# board_ders.net
KiCad netlist of a schematic drawn in EAGLE
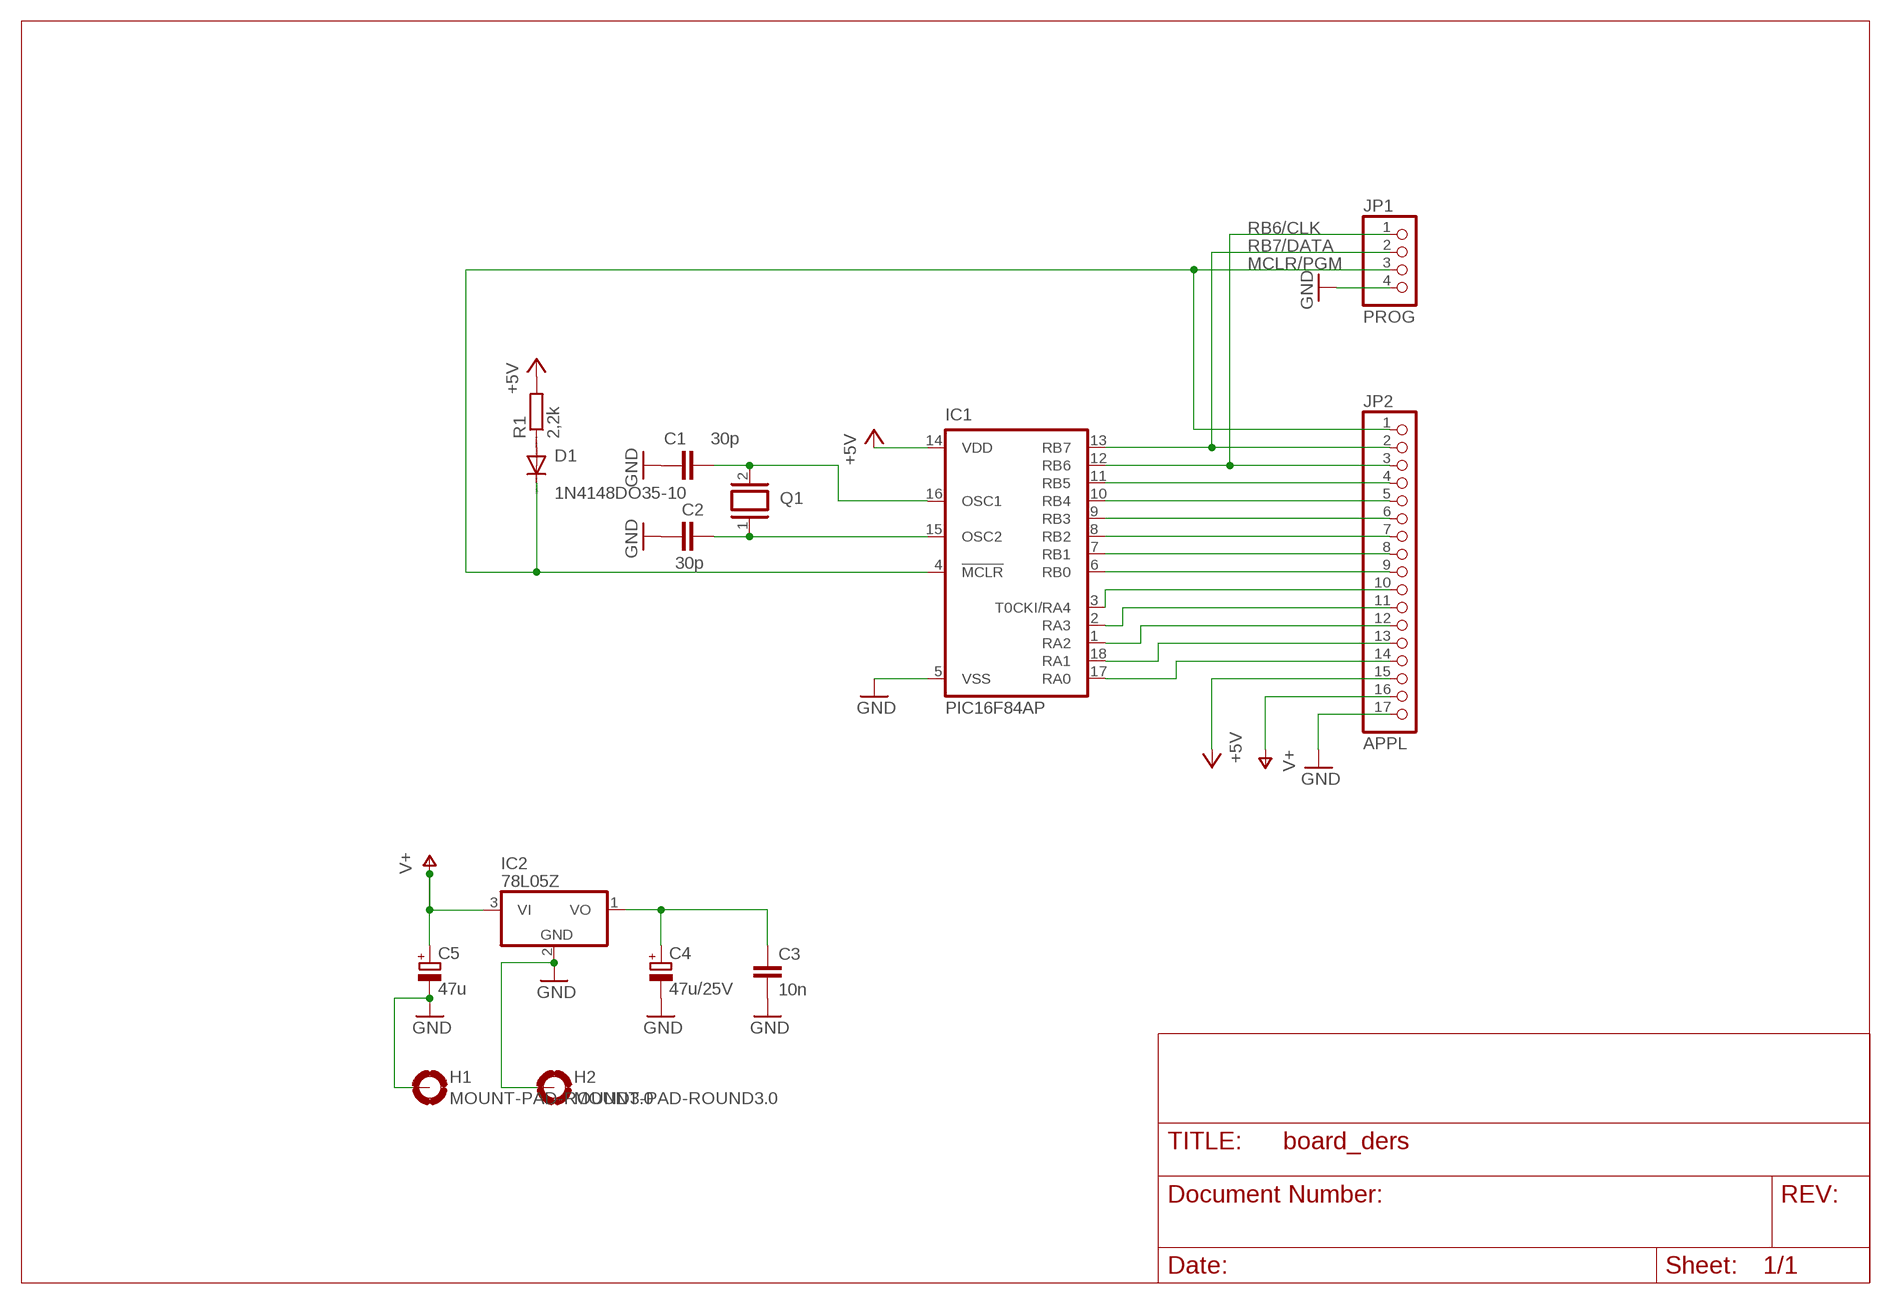
[diagram p0: schematic, sheet 1]

(export (version "E")
  (design (tool "Eeschema 10.0.6"))
  (components
    (comp (ref "C1")
      (value "30p")
      (footprint "eagle-import:C1206")
      (libsource (lib "eagle-import") (part "C-EUC1206"))
    )
    (comp (ref "C2")
      (value "30p")
      (footprint "eagle-import:C1206")
      (libsource (lib "eagle-import") (part "C-EUC1206"))
    )
    (comp (ref "C3")
      (value "10n")
      (footprint "eagle-import:C025-025X050")
      (libsource (lib "eagle-import") (part "C-EU025-025X050"))
    )
    (comp (ref "C4")
      (value "47u/25V")
      (footprint "eagle-import:TAP5-45")
      (libsource (lib "eagle-import") (part "CPOL-EUTAP5-45"))
    )
    (comp (ref "C5")
      (value "47u")
      (footprint "eagle-import:TAP5-45")
      (libsource (lib "eagle-import") (part "CPOL-EUTAP5-45"))
    )
    (comp (ref "D1")
      (value "1N4148DO35-10")
      (footprint "eagle-import:DO35-10")
      (libsource (lib "eagle-import") (part "1N4148DO35-10"))
    )
    (comp (ref "H1")
      (value "MOUNT-PAD-ROUND3.0")
      (footprint "eagle-import:3,0-PAD")
      (libsource (lib "eagle-import") (part "MOUNT-PAD-ROUND3.0"))
    )
    (comp (ref "H2")
      (value "MOUNT-PAD-ROUND3.0")
      (footprint "eagle-import:3,0-PAD")
      (libsource (lib "eagle-import") (part "MOUNT-PAD-ROUND3.0"))
    )
    (comp (ref "IC1")
      (value "PIC16F84AP")
      (footprint "eagle-import:DIL18")
      (fields (field (name "MF") "MICROCHIP") (field (name "MPN") "PIC16F84A-04I/P"))
      (libsource (lib "eagle-import") (part "PIC16F8P4A"))
    )
    (comp (ref "IC2")
      (value "78L05Z")
      (footprint "eagle-import:TO92")
      (libsource (lib "eagle-import") (part "78ZL05"))
    )
    (comp (ref "JP1")
      (value "PROG")
      (footprint "eagle-import:1X04")
      (libsource (lib "eagle-import") (part "PINHD-1X4"))
    )
    (comp (ref "JP2")
      (value "APPL")
      (footprint "eagle-import:1X17")
      (libsource (lib "eagle-import") (part "PINHD-1X17"))
    )
    (comp (ref "Q1")
      (value "XTAL/S")
      (footprint "eagle-import:QS")
      (libsource (lib "eagle-import") (part "XTAL/S"))
    )
    (comp (ref "R1")
      (value "2,2k")
      (footprint "eagle-import:R1206")
      (libsource (lib "eagle-import") (part "R-EU_R1206"))
    )
  )
  (nets
    (net (code "1") (name "+5V") (class "Default")
      (node (ref "IC1") (pin "14") (pinfunction "VDD_14") (pintype "power_in"))
      (node (ref "JP2") (pin "15") (pinfunction "15_15") (pintype "passive"))
      (node (ref "R1") (pin "2") (pinfunction "2_2") (pintype "passive"))
    )
    (net (code "2") (name "/MCLR{slash}PGM") (class "Default")
      (node (ref "D1") (pin "C") (pinfunction "C_C") (pintype "passive"))
      (node (ref "IC1") (pin "4") (pinfunction "~{MCLR}_4") (pintype "input"))
      (node (ref "JP1") (pin "3") (pinfunction "3_3") (pintype "passive"))
      (node (ref "JP2") (pin "1") (pinfunction "1_1") (pintype "passive"))
    )
    (net (code "3") (name "/RB6{slash}CLK") (class "Default")
      (node (ref "IC1") (pin "12") (pinfunction "RB6_12") (pintype "bidirectional"))
      (node (ref "JP1") (pin "1") (pinfunction "1_1") (pintype "passive"))
      (node (ref "JP2") (pin "3") (pinfunction "3_3") (pintype "passive"))
    )
    (net (code "4") (name "/RB7{slash}DATA") (class "Default")
      (node (ref "IC1") (pin "13") (pinfunction "RB7_13") (pintype "bidirectional"))
      (node (ref "JP1") (pin "2") (pinfunction "2_2") (pintype "passive"))
      (node (ref "JP2") (pin "2") (pinfunction "2_2") (pintype "passive"))
    )
    (net (code "5") (name "GND") (class "Default")
      (node (ref "C1") (pin "1") (pinfunction "1_1") (pintype "passive"))
      (node (ref "C2") (pin "1") (pinfunction "1_1") (pintype "passive"))
      (node (ref "C3") (pin "2") (pinfunction "2_2") (pintype "passive"))
      (node (ref "C4") (pin "-") (pinfunction "-_-") (pintype "passive"))
      (node (ref "C5") (pin "-") (pinfunction "-_-") (pintype "passive"))
      (node (ref "H1") (pin "B3,0") (pinfunction "MOUNT_B3,0") (pintype "passive"))
      (node (ref "H2") (pin "B3,0") (pinfunction "MOUNT_B3,0") (pintype "passive"))
      (node (ref "IC1") (pin "5") (pinfunction "VSS_5") (pintype "power_in"))
      (node (ref "IC2") (pin "2") (pinfunction "GND_2") (pintype "passive"))
      (node (ref "JP1") (pin "4") (pinfunction "4_4") (pintype "passive"))
      (node (ref "JP2") (pin "17") (pinfunction "17_17") (pintype "passive"))
    )
    (net (code "6") (name "Net-(D1-PadA)") (class "Default")
      (node (ref "D1") (pin "A") (pinfunction "A_A") (pintype "passive"))
      (node (ref "R1") (pin "1") (pinfunction "1_1") (pintype "passive"))
    )
    (net (code "7") (name "Net-(IC1-OSC1)") (class "Default")
      (node (ref "C1") (pin "2") (pinfunction "2_2") (pintype "passive"))
      (node (ref "IC1") (pin "16") (pinfunction "OSC1_16") (pintype "input"))
      (node (ref "Q1") (pin "2") (pinfunction "2_2") (pintype "passive"))
    )
    (net (code "8") (name "Net-(IC1-OSC2)") (class "Default")
      (node (ref "C2") (pin "2") (pinfunction "2_2") (pintype "passive"))
      (node (ref "IC1") (pin "15") (pinfunction "OSC2_15") (pintype "output"))
      (node (ref "Q1") (pin "1") (pinfunction "1_1") (pintype "passive"))
    )
    (net (code "9") (name "Net-(IC1-RA0)") (class "Default")
      (node (ref "IC1") (pin "17") (pinfunction "RA0_17") (pintype "bidirectional"))
      (node (ref "JP2") (pin "14") (pinfunction "14_14") (pintype "passive"))
    )
    (net (code "10") (name "Net-(IC1-RA1)") (class "Default")
      (node (ref "IC1") (pin "18") (pinfunction "RA1_18") (pintype "bidirectional"))
      (node (ref "JP2") (pin "13") (pinfunction "13_13") (pintype "passive"))
    )
    (net (code "11") (name "Net-(IC1-RA2)") (class "Default")
      (node (ref "IC1") (pin "1") (pinfunction "RA2_1") (pintype "bidirectional"))
      (node (ref "JP2") (pin "12") (pinfunction "12_12") (pintype "passive"))
    )
    (net (code "12") (name "Net-(IC1-RA3)") (class "Default")
      (node (ref "IC1") (pin "2") (pinfunction "RA3_2") (pintype "bidirectional"))
      (node (ref "JP2") (pin "11") (pinfunction "11_11") (pintype "passive"))
    )
    (net (code "13") (name "Net-(IC1-RB0)") (class "Default")
      (node (ref "IC1") (pin "6") (pinfunction "RB0_6") (pintype "bidirectional"))
      (node (ref "JP2") (pin "9") (pinfunction "9_9") (pintype "passive"))
    )
    (net (code "14") (name "Net-(IC1-RB1)") (class "Default")
      (node (ref "IC1") (pin "7") (pinfunction "RB1_7") (pintype "bidirectional"))
      (node (ref "JP2") (pin "8") (pinfunction "8_8") (pintype "passive"))
    )
    (net (code "15") (name "Net-(IC1-RB2)") (class "Default")
      (node (ref "IC1") (pin "8") (pinfunction "RB2_8") (pintype "bidirectional"))
      (node (ref "JP2") (pin "7") (pinfunction "7_7") (pintype "passive"))
    )
    (net (code "16") (name "Net-(IC1-RB3)") (class "Default")
      (node (ref "IC1") (pin "9") (pinfunction "RB3_9") (pintype "bidirectional"))
      (node (ref "JP2") (pin "6") (pinfunction "6_6") (pintype "passive"))
    )
    (net (code "17") (name "Net-(IC1-RB4)") (class "Default")
      (node (ref "IC1") (pin "10") (pinfunction "RB4_10") (pintype "bidirectional"))
      (node (ref "JP2") (pin "5") (pinfunction "5_5") (pintype "passive"))
    )
    (net (code "18") (name "Net-(IC1-RB5)") (class "Default")
      (node (ref "IC1") (pin "11") (pinfunction "RB5_11") (pintype "bidirectional"))
      (node (ref "JP2") (pin "4") (pinfunction "4_4") (pintype "passive"))
    )
    (net (code "19") (name "Net-(IC1-T0CKI{slash}RA4)") (class "Default")
      (node (ref "IC1") (pin "3") (pinfunction "T0CKI/RA4_3") (pintype "bidirectional"))
      (node (ref "JP2") (pin "10") (pinfunction "10_10") (pintype "passive"))
    )
    (net (code "20") (name "Net-(IC2-VO)") (class "Default")
      (node (ref "C3") (pin "1") (pinfunction "1_1") (pintype "passive"))
      (node (ref "C4") (pin "+") (pinfunction "+_+") (pintype "passive"))
      (node (ref "IC2") (pin "1") (pinfunction "VO_1") (pintype "passive"))
    )
    (net (code "21") (name "V+") (class "Default")
      (node (ref "C5") (pin "+") (pinfunction "+_+") (pintype "passive"))
      (node (ref "IC2") (pin "3") (pinfunction "VI_3") (pintype "input"))
      (node (ref "JP2") (pin "16") (pinfunction "16_16") (pintype "passive"))
    )
  )
)
